# Questao4_Com_E_Sem_i2c.net
KiCad netlist of a schematic drawn in EAGLE
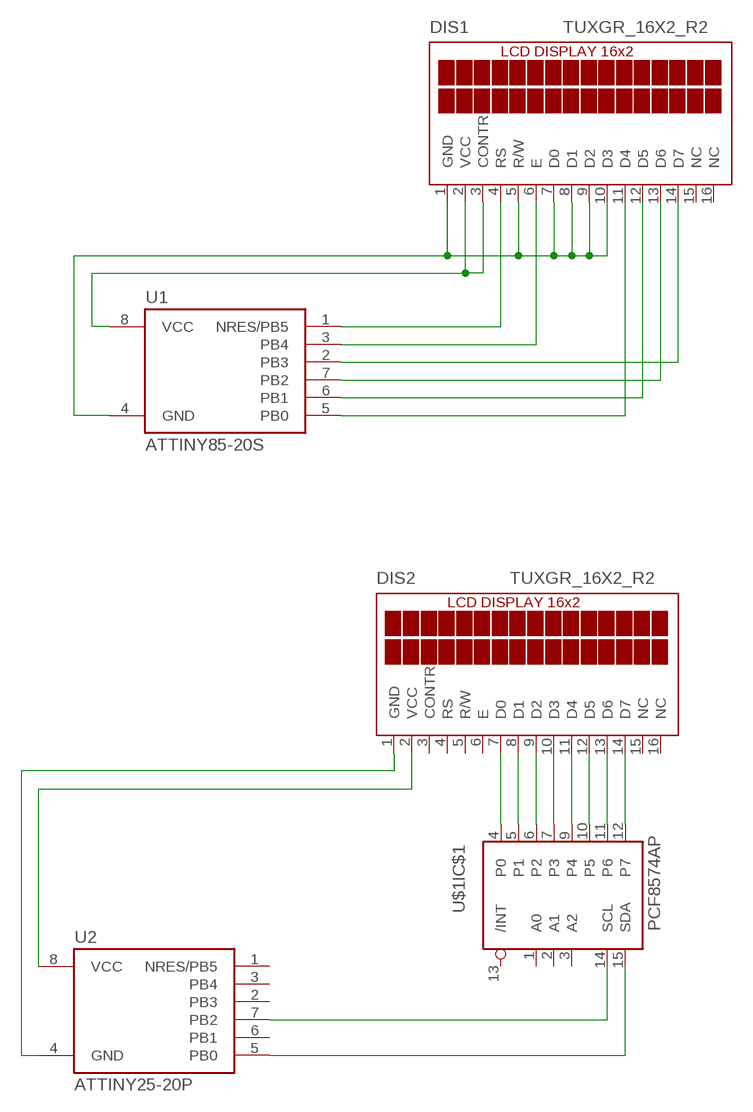
[diagram p0: schematic, sheet 1]

(export (version "E")
  (design (tool "Eeschema 10.0.6"))
  (components
    (comp (ref "DIS1")
      (value "TUXGR_16X2_R2")
      (footprint "eagle-import:TUXGR_16X2_R2")
      (libsource (lib "eagle-import") (part "TUXGR_16X2_R2"))
    )
    (comp (ref "DIS2")
      (value "TUXGR_16X2_R2")
      (footprint "eagle-import:TUXGR_16X2_R2")
      (libsource (lib "eagle-import") (part "TUXGR_16X2_R2"))
    )
    (comp (ref "U$1")
      (value "PCF8574AP")
      (footprint "eagle-import:DIL16")
      (libsource (lib "eagle-import") (part "PCF8574AP"))
    )
    (comp (ref "U1")
      (value "ATTINY85-20S")
      (footprint "eagle-import:SOIC8_EIAJ_208MIL")
      (libsource (lib "eagle-import") (part "ATTINY85S-20"))
    )
    (comp (ref "U2")
      (value "ATTINY25-20P")
      (footprint "eagle-import:PDIP08_300MIL")
      (libsource (lib "eagle-import") (part "ATTINY25P-20"))
    )
  )
  (nets
    (net (code "1") (name "Net-(DIS1-CONTR)") (class "Default")
      (node (ref "DIS1") (pin "2") (pinfunction "VCC_2") (pintype "power_in"))
      (node (ref "DIS1") (pin "3") (pinfunction "CONTR_3") (pintype "input"))
      (node (ref "U1") (pin "8") (pinfunction "VCC_8") (pintype "power_in"))
    )
    (net (code "2") (name "Net-(DIS1-D0)") (class "Default")
      (node (ref "DIS1") (pin "1") (pinfunction "GND_1") (pintype "power_in"))
      (node (ref "DIS1") (pin "10") (pinfunction "D3_10") (pintype "input"))
      (node (ref "DIS1") (pin "5") (pinfunction "R/W_5") (pintype "input"))
      (node (ref "DIS1") (pin "7") (pinfunction "D0_7") (pintype "input"))
      (node (ref "DIS1") (pin "8") (pinfunction "D1_8") (pintype "input"))
      (node (ref "DIS1") (pin "9") (pinfunction "D2_9") (pintype "input"))
      (node (ref "U1") (pin "4") (pinfunction "GND_4") (pintype "power_in"))
    )
    (net (code "3") (name "Net-(DIS1-D4)") (class "Default")
      (node (ref "DIS1") (pin "11") (pinfunction "D4_11") (pintype "input"))
      (node (ref "U1") (pin "5") (pinfunction "PB0_5") (pintype "bidirectional"))
    )
    (net (code "4") (name "Net-(DIS1-D5)") (class "Default")
      (node (ref "DIS1") (pin "12") (pinfunction "D5_12") (pintype "input"))
      (node (ref "U1") (pin "6") (pinfunction "PB1_6") (pintype "bidirectional"))
    )
    (net (code "5") (name "Net-(DIS1-D6)") (class "Default")
      (node (ref "DIS1") (pin "13") (pinfunction "D6_13") (pintype "input"))
      (node (ref "U1") (pin "7") (pinfunction "PB2_7") (pintype "bidirectional"))
    )
    (net (code "6") (name "Net-(DIS1-D7)") (class "Default")
      (node (ref "DIS1") (pin "14") (pinfunction "D7_14") (pintype "input"))
      (node (ref "U1") (pin "2") (pinfunction "PB3_2") (pintype "bidirectional"))
    )
    (net (code "7") (name "Net-(DIS1-E)") (class "Default")
      (node (ref "DIS1") (pin "6") (pinfunction "E_6") (pintype "input"))
      (node (ref "U1") (pin "3") (pinfunction "PB4_3") (pintype "bidirectional"))
    )
    (net (code "8") (name "Net-(DIS1-RS)") (class "Default")
      (node (ref "DIS1") (pin "4") (pinfunction "RS_4") (pintype "input"))
      (node (ref "U1") (pin "1") (pinfunction "NRES/PB5_1") (pintype "bidirectional"))
    )
    (net (code "9") (name "Net-(DIS2-D0)") (class "Default")
      (node (ref "DIS2") (pin "7") (pinfunction "D0_7") (pintype "input"))
      (node (ref "U$1") (pin "4") (pinfunction "P0_4") (pintype "bidirectional"))
    )
    (net (code "10") (name "Net-(DIS2-D1)") (class "Default")
      (node (ref "DIS2") (pin "8") (pinfunction "D1_8") (pintype "input"))
      (node (ref "U$1") (pin "5") (pinfunction "P1_5") (pintype "bidirectional"))
    )
    (net (code "11") (name "Net-(DIS2-D2)") (class "Default")
      (node (ref "DIS2") (pin "9") (pinfunction "D2_9") (pintype "input"))
      (node (ref "U$1") (pin "6") (pinfunction "P2_6") (pintype "bidirectional"))
    )
    (net (code "12") (name "Net-(DIS2-D3)") (class "Default")
      (node (ref "DIS2") (pin "10") (pinfunction "D3_10") (pintype "input"))
      (node (ref "U$1") (pin "7") (pinfunction "P3_7") (pintype "bidirectional"))
    )
    (net (code "13") (name "Net-(DIS2-D4)") (class "Default")
      (node (ref "DIS2") (pin "11") (pinfunction "D4_11") (pintype "input"))
      (node (ref "U$1") (pin "9") (pinfunction "P4_9") (pintype "bidirectional"))
    )
    (net (code "14") (name "Net-(DIS2-D5)") (class "Default")
      (node (ref "DIS2") (pin "12") (pinfunction "D5_12") (pintype "input"))
      (node (ref "U$1") (pin "10") (pinfunction "P5_10") (pintype "bidirectional"))
    )
    (net (code "15") (name "Net-(DIS2-D6)") (class "Default")
      (node (ref "DIS2") (pin "13") (pinfunction "D6_13") (pintype "input"))
      (node (ref "U$1") (pin "11") (pinfunction "P6_11") (pintype "bidirectional"))
    )
    (net (code "16") (name "Net-(DIS2-D7)") (class "Default")
      (node (ref "DIS2") (pin "14") (pinfunction "D7_14") (pintype "input"))
      (node (ref "U$1") (pin "12") (pinfunction "P7_12") (pintype "bidirectional"))
    )
    (net (code "17") (name "Net-(DIS2-GND)") (class "Default")
      (node (ref "DIS2") (pin "1") (pinfunction "GND_1") (pintype "power_in"))
      (node (ref "U2") (pin "4") (pinfunction "GND_4") (pintype "power_in"))
    )
    (net (code "18") (name "Net-(DIS2-VCC)") (class "Default")
      (node (ref "DIS2") (pin "2") (pinfunction "VCC_2") (pintype "power_in"))
      (node (ref "U2") (pin "8") (pinfunction "VCC_8") (pintype "power_in"))
    )
    (net (code "19") (name "Net-(U$1A-SCL)") (class "Default")
      (node (ref "U$1") (pin "14") (pinfunction "SCL_14") (pintype "input"))
      (node (ref "U2") (pin "7") (pinfunction "PB2_7") (pintype "bidirectional"))
    )
    (net (code "20") (name "Net-(U$1A-SDA)") (class "Default")
      (node (ref "U$1") (pin "15") (pinfunction "SDA_15") (pintype "bidirectional"))
      (node (ref "U2") (pin "5") (pinfunction "PB0_5") (pintype "bidirectional"))
    )
    (net (code "21") (name "unconnected-(DIS1-NC-Pad15)") (class "Default")
      (node (ref "DIS1") (pin "15") (pinfunction "NC_15") (pintype "no_connect"))
    )
    (net (code "22") (name "unconnected-(DIS1-NC-Pad16)") (class "Default")
      (node (ref "DIS1") (pin "16") (pinfunction "NC_16") (pintype "no_connect"))
    )
    (net (code "23") (name "unconnected-(DIS2-CONTR-Pad3)") (class "Default")
      (node (ref "DIS2") (pin "3") (pinfunction "CONTR_3") (pintype "input"))
    )
    (net (code "24") (name "unconnected-(DIS2-E-Pad6)") (class "Default")
      (node (ref "DIS2") (pin "6") (pinfunction "E_6") (pintype "input"))
    )
    (net (code "25") (name "unconnected-(DIS2-NC-Pad15)") (class "Default")
      (node (ref "DIS2") (pin "15") (pinfunction "NC_15") (pintype "no_connect"))
    )
    (net (code "26") (name "unconnected-(DIS2-NC-Pad16)") (class "Default")
      (node (ref "DIS2") (pin "16") (pinfunction "NC_16") (pintype "no_connect"))
    )
    (net (code "27") (name "unconnected-(DIS2-RS-Pad4)") (class "Default")
      (node (ref "DIS2") (pin "4") (pinfunction "RS_4") (pintype "input"))
    )
    (net (code "28") (name "unconnected-(DIS2-R{slash}W-Pad5)") (class "Default")
      (node (ref "DIS2") (pin "5") (pinfunction "R/W_5") (pintype "input"))
    )
    (net (code "29") (name "unconnected-(U$1A-A0-Pad1)") (class "Default")
      (node (ref "U$1") (pin "1") (pinfunction "A0_1") (pintype "input"))
    )
    (net (code "30") (name "unconnected-(U$1A-A1-Pad2)") (class "Default")
      (node (ref "U$1") (pin "2") (pinfunction "A1_2") (pintype "input"))
    )
    (net (code "31") (name "unconnected-(U$1A-A2-Pad3)") (class "Default")
      (node (ref "U$1") (pin "3") (pinfunction "A2_3") (pintype "input"))
    )
    (net (code "32") (name "unconnected-(U$1A-{slash}INT-Pad13)") (class "Default")
      (node (ref "U$1") (pin "13") (pinfunction "/INT_13") (pintype "output"))
    )
    (net (code "33") (name "unconnected-(U2-NRES{slash}PB5-Pad1)") (class "Default")
      (node (ref "U2") (pin "1") (pinfunction "NRES/PB5_1") (pintype "bidirectional"))
    )
    (net (code "34") (name "unconnected-(U2-PB1-Pad6)") (class "Default")
      (node (ref "U2") (pin "6") (pinfunction "PB1_6") (pintype "bidirectional"))
    )
    (net (code "35") (name "unconnected-(U2-PB3-Pad2)") (class "Default")
      (node (ref "U2") (pin "2") (pinfunction "PB3_2") (pintype "bidirectional"))
    )
    (net (code "36") (name "unconnected-(U2-PB4-Pad3)") (class "Default")
      (node (ref "U2") (pin "3") (pinfunction "PB4_3") (pintype "bidirectional"))
    )
  )
)
